# circuito_control.net
KiCad netlist of a schematic drawn in EAGLE
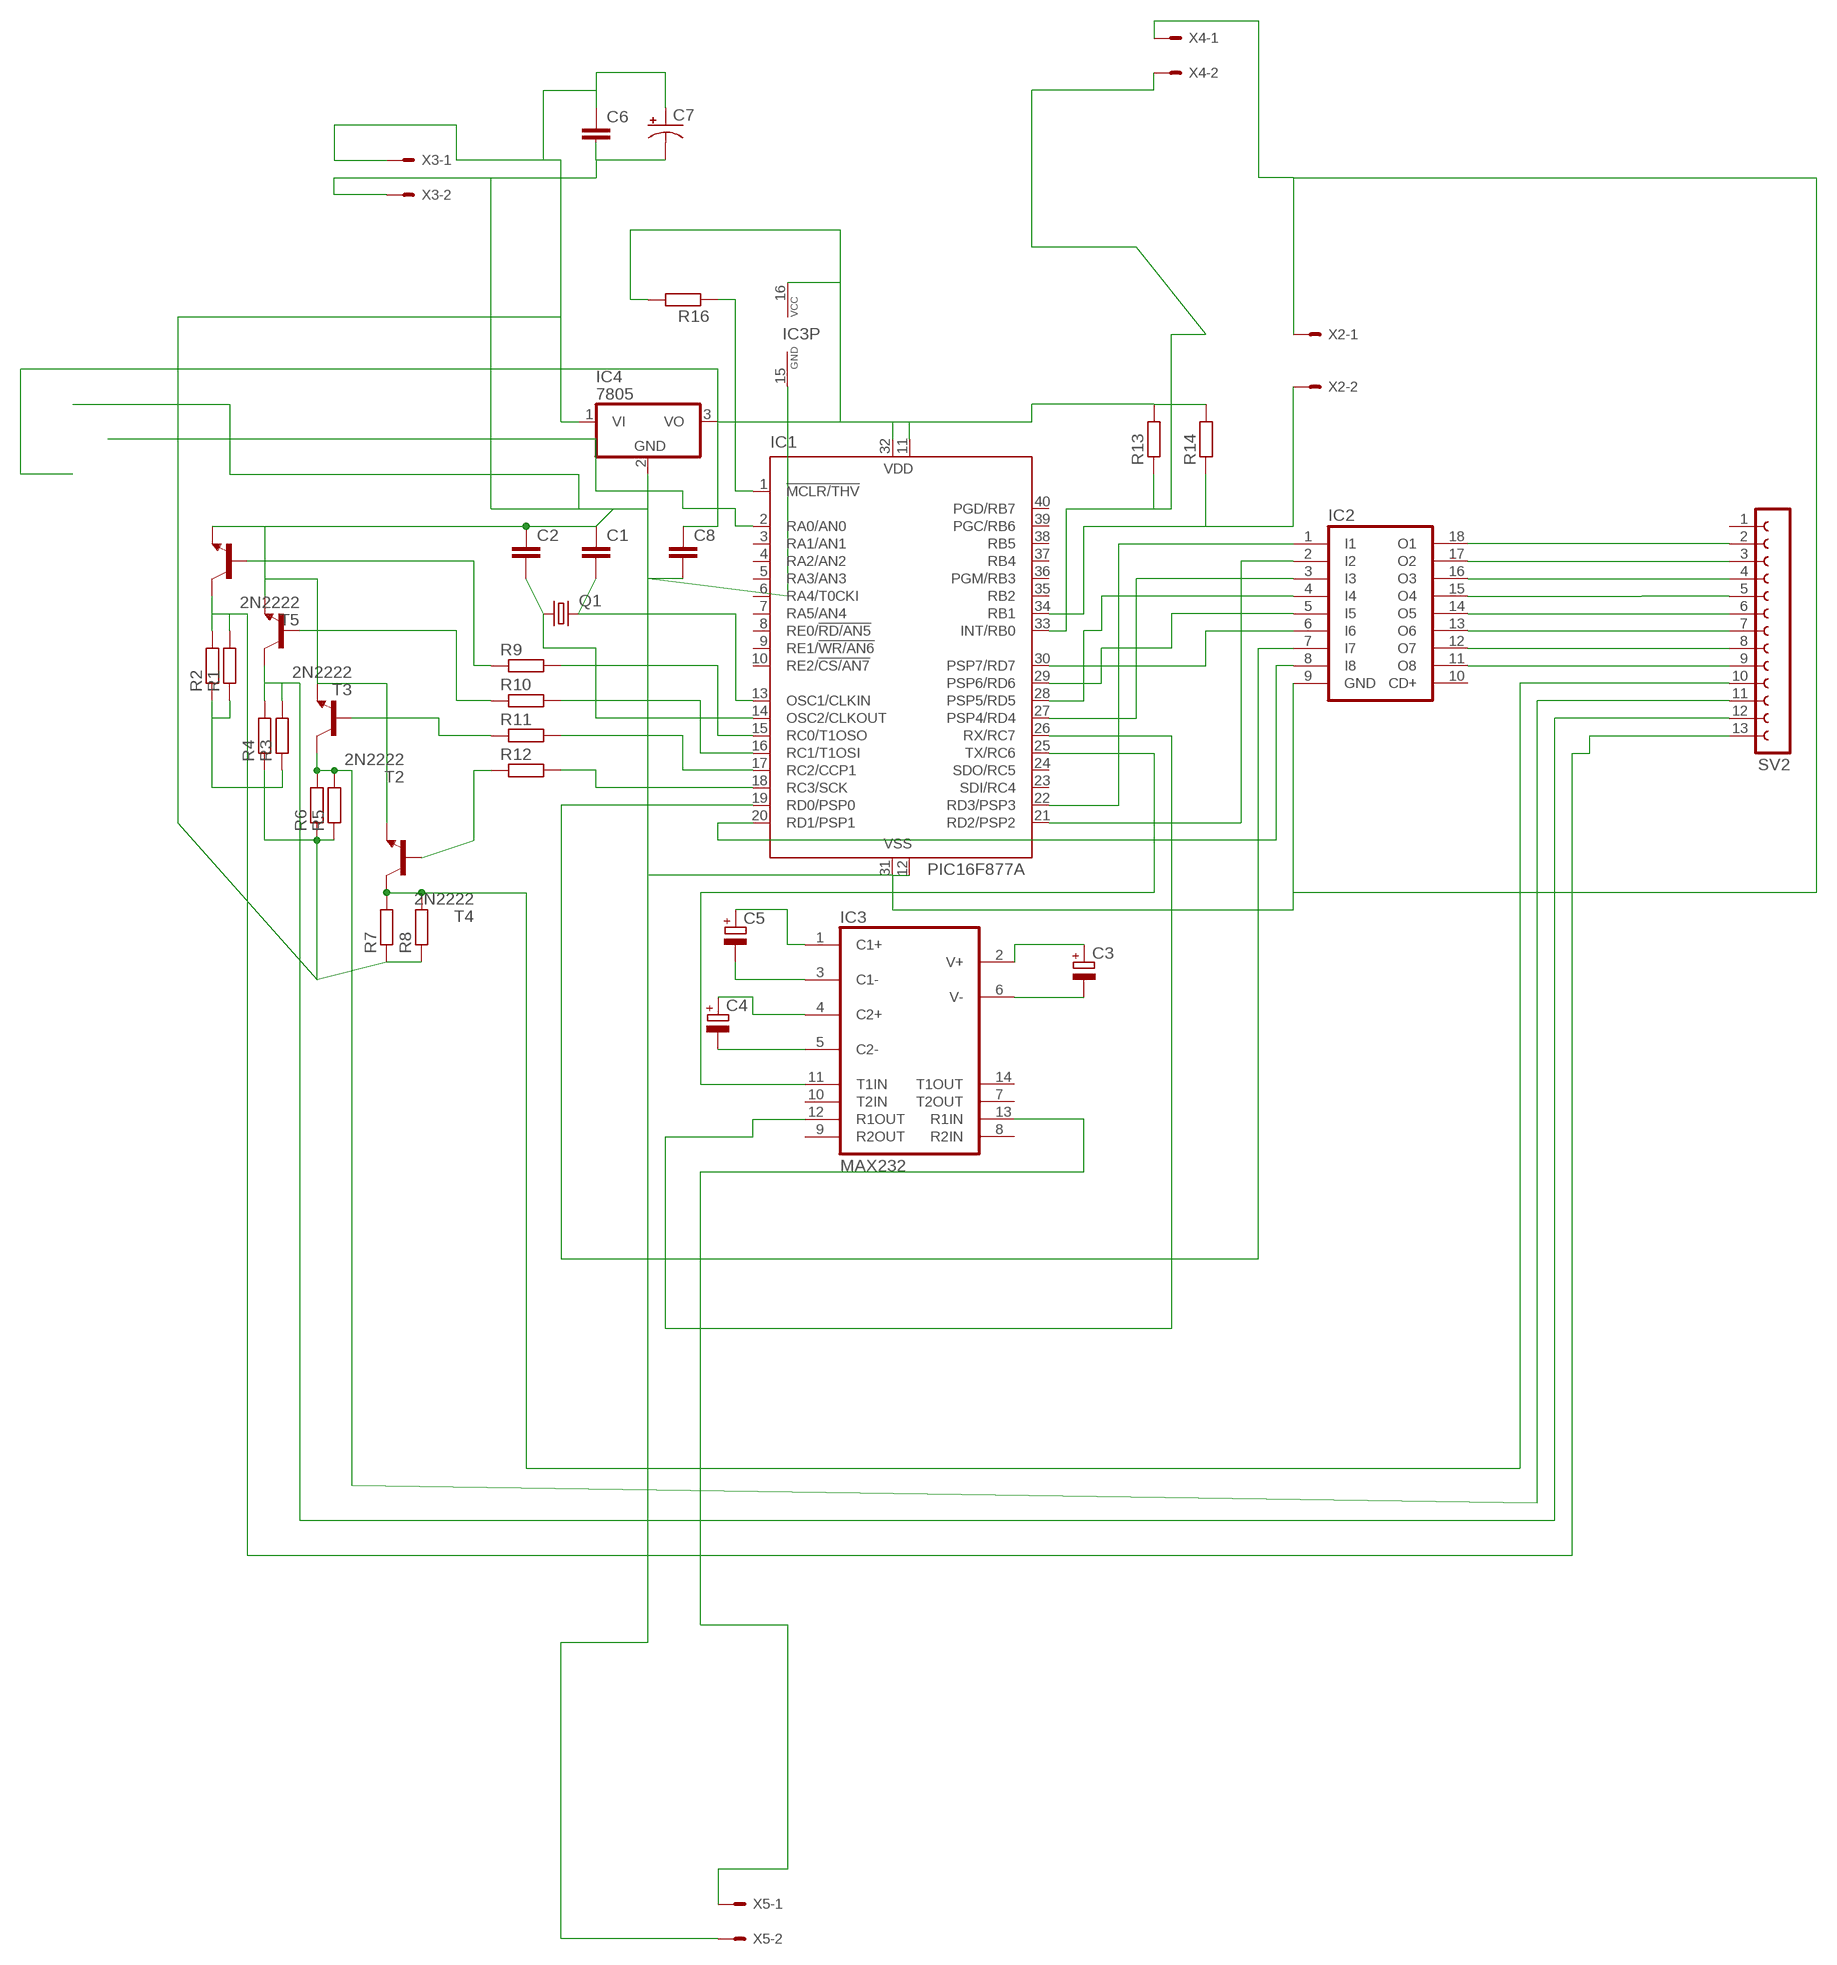
[diagram p0: schematic, sheet 1]

(export (version "E")
  (design (tool "Eeschema 10.0.6"))
  (components
    (comp (ref "C1")
      (value "C-EU025-025X050")
      (footprint "eagle-import:C025-025X050")
      (libsource (lib "eagle-import") (part "C-EU025-025X050"))
    )
    (comp (ref "C2")
      (value "C-EU025-025X050")
      (footprint "eagle-import:C025-025X050")
      (libsource (lib "eagle-import") (part "C-EU025-025X050"))
    )
    (comp (ref "C3")
      (value "CPOL-EUE1.8-4")
      (footprint "eagle-import:E1,8-4")
      (libsource (lib "eagle-import") (part "CPOL-EUE1.8-4"))
    )
    (comp (ref "C4")
      (value "CPOL-EUE1.8-4")
      (footprint "eagle-import:E1,8-4")
      (libsource (lib "eagle-import") (part "CPOL-EUE1.8-4"))
    )
    (comp (ref "C5")
      (value "CPOL-EUE1.8-4")
      (footprint "eagle-import:E1,8-4")
      (libsource (lib "eagle-import") (part "CPOL-EUE1.8-4"))
    )
    (comp (ref "C6")
      (value "C-EU025-025X050")
      (footprint "eagle-import:C025-025X050")
      (libsource (lib "eagle-import") (part "C-EU025-025X050"))
    )
    (comp (ref "C7")
      (value "CPOL-USE5-10.5")
      (footprint "eagle-import:E5-10,5")
      (libsource (lib "eagle-import") (part "CPOL-USE5-10.5"))
    )
    (comp (ref "C8")
      (value "C-EU025-025X050")
      (footprint "eagle-import:C025-025X050")
      (libsource (lib "eagle-import") (part "C-EU025-025X050"))
    )
    (comp (ref "IC1")
      (value "PIC16F877A")
      (footprint "eagle-import:DIL40")
      (fields (field (name "MF") "MICROCHIP") (field (name "MPN") "PIC16F877-04/P"))
      (libsource (lib "eagle-import") (part "PIC16F87P7"))
    )
    (comp (ref "IC2")
      (value "ULN2803A")
      (footprint "eagle-import:DIL18")
      (libsource (lib "eagle-import") (part "ULN2803A"))
    )
    (comp (ref "IC3")
      (value "MAX232")
      (footprint "eagle-import:DIL16")
      (fields (field (name "MF") "MAXIM") (field (name "MPN") "MAX232ACPE+"))
      (libsource (lib "eagle-import") (part "MAX232"))
    )
    (comp (ref "IC4")
      (value "7805")
      (footprint "eagle-import:TO220V")
      (libsource (lib "eagle-import") (part "78TV05"))
    )
    (comp (ref "Q1")
      (value "CRYSTALHC49U70")
      (footprint "eagle-import:HC49U70")
      (libsource (lib "eagle-import") (part "CRYSTALHC49U70"))
    )
    (comp (ref "R1")
      (value "R-EU_0411/15")
      (footprint "eagle-import:0411_15")
      (libsource (lib "eagle-import") (part "R-EU_0411/15"))
    )
    (comp (ref "R2")
      (value "R-EU_0411/15")
      (footprint "eagle-import:0411_15")
      (libsource (lib "eagle-import") (part "R-EU_0411/15"))
    )
    (comp (ref "R3")
      (value "R-EU_0411/15")
      (footprint "eagle-import:0411_15")
      (libsource (lib "eagle-import") (part "R-EU_0411/15"))
    )
    (comp (ref "R4")
      (value "R-EU_0411/15")
      (footprint "eagle-import:0411_15")
      (libsource (lib "eagle-import") (part "R-EU_0411/15"))
    )
    (comp (ref "R5")
      (value "R-EU_0411/15")
      (footprint "eagle-import:0411_15")
      (libsource (lib "eagle-import") (part "R-EU_0411/15"))
    )
    (comp (ref "R6")
      (value "R-EU_0411/15")
      (footprint "eagle-import:0411_15")
      (libsource (lib "eagle-import") (part "R-EU_0411/15"))
    )
    (comp (ref "R7")
      (value "R-EU_0411/15")
      (footprint "eagle-import:0411_15")
      (libsource (lib "eagle-import") (part "R-EU_0411/15"))
    )
    (comp (ref "R8")
      (value "R-EU_0411/15")
      (footprint "eagle-import:0411_15")
      (libsource (lib "eagle-import") (part "R-EU_0411/15"))
    )
    (comp (ref "R9")
      (value "R-EU_0207/7")
      (footprint "eagle-import:0207_7")
      (libsource (lib "eagle-import") (part "resistor_R-EU_0207/7"))
    )
    (comp (ref "R10")
      (value "R-EU_0207/7")
      (footprint "eagle-import:0207_7")
      (libsource (lib "eagle-import") (part "resistor_R-EU_0207/7"))
    )
    (comp (ref "R11")
      (value "R-EU_0207/7")
      (footprint "eagle-import:0207_7")
      (libsource (lib "eagle-import") (part "resistor_R-EU_0207/7"))
    )
    (comp (ref "R12")
      (value "R-EU_0207/7")
      (footprint "eagle-import:0207_7")
      (libsource (lib "eagle-import") (part "resistor_R-EU_0207/7"))
    )
    (comp (ref "R13")
      (value "R-EU_0207/7")
      (footprint "eagle-import:0207_7")
      (libsource (lib "eagle-import") (part "resistor_R-EU_0207/7"))
    )
    (comp (ref "R14")
      (value "R-EU_0207/7")
      (footprint "eagle-import:0207_7")
      (libsource (lib "eagle-import") (part "resistor_R-EU_0207/7"))
    )
    (comp (ref "R16")
      (value "R-EU_0207/7")
      (footprint "eagle-import:0207_7")
      (libsource (lib "eagle-import") (part "resistor_R-EU_0207/7"))
    )
    (comp (ref "SV2")
      (value "FE13-1")
      (footprint "eagle-import:FE13")
      (libsource (lib "eagle-import") (part "FE13-1"))
    )
    (comp (ref "T2")
      (value "2N2222")
      (footprint "eagle-import:TO18")
      (libsource (lib "eagle-import") (part "2N2222"))
    )
    (comp (ref "T3")
      (value "2N2222")
      (footprint "eagle-import:TO18")
      (libsource (lib "eagle-import") (part "2N2222"))
    )
    (comp (ref "T4")
      (value "2N2222")
      (footprint "eagle-import:TO18")
      (libsource (lib "eagle-import") (part "2N2222"))
    )
    (comp (ref "T5")
      (value "2N2222")
      (footprint "eagle-import:TO18")
      (libsource (lib "eagle-import") (part "2N2222"))
    )
    (comp (ref "X2")
      (value "KK-156-2")
      (footprint "eagle-import:KK-156-2")
      (libsource (lib "eagle-import") (part "KK-156-2"))
    )
    (comp (ref "X3")
      (value "KK-156-2")
      (footprint "eagle-import:KK-156-2")
      (libsource (lib "eagle-import") (part "KK-156-2"))
    )
    (comp (ref "X4")
      (value "KK-156-2")
      (footprint "eagle-import:KK-156-2")
      (libsource (lib "eagle-import") (part "KK-156-2"))
    )
    (comp (ref "X5")
      (value "KK-156-2")
      (footprint "eagle-import:KK-156-2")
      (fields (field (name "OC_FARNELL") "unknown") (field (name "OC_NEWARK") "unknown"))
      (libsource (lib "eagle-import") (part "KK-156-2"))
    )
  )
  (nets
    (net (code "1") (name "Net-(IC1-INT{slash}RB0)") (class "Default")
      (node (ref "IC1") (pin "33") (pinfunction "INT/RB0_33") (pintype "bidirectional"))
      (node (ref "R13") (pin "1") (pinfunction "1_1") (pintype "passive"))
      (node (ref "X4") (pin "2") (pinfunction "S_2") (pintype "passive"))
    )
    (net (code "2") (name "Net-(IC1-OSC1{slash}CLKIN)") (class "Default")
      (node (ref "C1") (pin "2") (pinfunction "2_2") (pintype "passive"))
      (node (ref "IC1") (pin "13") (pinfunction "OSC1/CLKIN_13") (pintype "input"))
      (node (ref "Q1") (pin "2") (pinfunction "2_2") (pintype "passive"))
    )
    (net (code "3") (name "Net-(IC1-OSC2{slash}CLKOUT)") (class "Default")
      (node (ref "C2") (pin "2") (pinfunction "2_2") (pintype "passive"))
      (node (ref "IC1") (pin "14") (pinfunction "OSC2/CLKOUT_14") (pintype "output"))
      (node (ref "Q1") (pin "1") (pinfunction "1_1") (pintype "passive"))
    )
    (net (code "4") (name "Net-(IC1-PSP4{slash}RD4)") (class "Default")
      (node (ref "IC1") (pin "27") (pinfunction "PSP4/RD4_27") (pintype "bidirectional"))
      (node (ref "IC2") (pin "3") (pinfunction "I3_3") (pintype "input"))
    )
    (net (code "5") (name "Net-(IC1-PSP5{slash}RD5)") (class "Default")
      (node (ref "IC1") (pin "28") (pinfunction "PSP5/RD5_28") (pintype "bidirectional"))
      (node (ref "IC2") (pin "4") (pinfunction "I4_4") (pintype "input"))
    )
    (net (code "6") (name "Net-(IC1-PSP6{slash}RD6)") (class "Default")
      (node (ref "IC1") (pin "29") (pinfunction "PSP6/RD6_29") (pintype "bidirectional"))
      (node (ref "IC2") (pin "5") (pinfunction "I5_5") (pintype "input"))
    )
    (net (code "7") (name "Net-(IC1-PSP7{slash}RD7)") (class "Default")
      (node (ref "IC1") (pin "30") (pinfunction "PSP7/RD7_30") (pintype "bidirectional"))
      (node (ref "IC2") (pin "6") (pinfunction "I6_6") (pintype "input"))
    )
    (net (code "8") (name "Net-(IC1-RB1)") (class "Default")
      (node (ref "IC1") (pin "34") (pinfunction "RB1_34") (pintype "bidirectional"))
      (node (ref "R14") (pin "1") (pinfunction "1_1") (pintype "passive"))
      (node (ref "X2") (pin "2") (pinfunction "S_2") (pintype "passive"))
    )
    (net (code "9") (name "Net-(IC1-RC0{slash}T1OSO)") (class "Default")
      (node (ref "IC1") (pin "15") (pinfunction "RC0/T1OSO_15") (pintype "bidirectional"))
      (node (ref "R9") (pin "2") (pinfunction "2_2") (pintype "passive"))
    )
    (net (code "10") (name "Net-(IC1-RC1{slash}T1OSI)") (class "Default")
      (node (ref "IC1") (pin "16") (pinfunction "RC1/T1OSI_16") (pintype "bidirectional"))
      (node (ref "R10") (pin "2") (pinfunction "2_2") (pintype "passive"))
    )
    (net (code "11") (name "Net-(IC1-RC2{slash}CCP1)") (class "Default")
      (node (ref "IC1") (pin "17") (pinfunction "RC2/CCP1_17") (pintype "bidirectional"))
      (node (ref "R11") (pin "2") (pinfunction "2_2") (pintype "passive"))
    )
    (net (code "12") (name "Net-(IC1-RC3{slash}SCK)") (class "Default")
      (node (ref "IC1") (pin "18") (pinfunction "RC3/SCK_18") (pintype "bidirectional"))
      (node (ref "R12") (pin "2") (pinfunction "2_2") (pintype "passive"))
    )
    (net (code "13") (name "Net-(IC1-RD0{slash}PSP0)") (class "Default")
      (node (ref "IC1") (pin "19") (pinfunction "RD0/PSP0_19") (pintype "bidirectional"))
      (node (ref "IC2") (pin "7") (pinfunction "I7_7") (pintype "input"))
    )
    (net (code "14") (name "Net-(IC1-RD1{slash}PSP1)") (class "Default")
      (node (ref "IC1") (pin "20") (pinfunction "RD1/PSP1_20") (pintype "bidirectional"))
      (node (ref "IC2") (pin "8") (pinfunction "I8_8") (pintype "input"))
    )
    (net (code "15") (name "Net-(IC1-RD2{slash}PSP2)") (class "Default")
      (node (ref "IC1") (pin "21") (pinfunction "RD2/PSP2_21") (pintype "bidirectional"))
      (node (ref "IC2") (pin "2") (pinfunction "I2_2") (pintype "input"))
    )
    (net (code "16") (name "Net-(IC1-RD3{slash}PSP3)") (class "Default")
      (node (ref "IC1") (pin "22") (pinfunction "RD3/PSP3_22") (pintype "bidirectional"))
      (node (ref "IC2") (pin "1") (pinfunction "I1_1") (pintype "input"))
    )
    (net (code "17") (name "Net-(IC1-RX{slash}RC7)") (class "Default")
      (node (ref "IC1") (pin "26") (pinfunction "RX/RC7_26") (pintype "bidirectional"))
      (node (ref "IC3") (pin "12") (pinfunction "R1OUT_12") (pintype "output"))
    )
    (net (code "18") (name "Net-(IC1-TX{slash}RC6)") (class "Default")
      (node (ref "IC1") (pin "25") (pinfunction "TX/RC6_25") (pintype "bidirectional"))
      (node (ref "IC3") (pin "11") (pinfunction "T1IN_11") (pintype "input"))
    )
    (net (code "19") (name "Net-(IC1-~{MCLR{slash}THV})") (class "Default")
      (node (ref "IC1") (pin "1") (pinfunction "~{MCLR/THV}_1") (pintype "input"))
      (node (ref "R16") (pin "1") (pinfunction "1_1") (pintype "passive"))
    )
    (net (code "20") (name "Net-(IC2-GND)") (class "Default")
      (node (ref "C1") (pin "1") (pinfunction "1_1") (pintype "passive"))
      (node (ref "C2") (pin "1") (pinfunction "1_1") (pintype "passive"))
      (node (ref "C6") (pin "2") (pinfunction "2_2") (pintype "passive"))
      (node (ref "C7") (pin "-") (pinfunction "-_-") (pintype "passive"))
      (node (ref "C8") (pin "2") (pinfunction "2_2") (pintype "passive"))
      (node (ref "IC1") (pin "12") (pinfunction "VSS_12") (pintype "power_in"))
      (node (ref "IC1") (pin "31") (pinfunction "VSS_31") (pintype "power_in"))
      (node (ref "IC2") (pin "9") (pinfunction "GND_9") (pintype "power_in"))
      (node (ref "IC3") (pin "15") (pinfunction "GND_15") (pintype "power_in"))
      (node (ref "IC4") (pin "2") (pinfunction "GND_2") (pintype "passive"))
      (node (ref "T2") (pin "1") (pinfunction "E_1") (pintype "passive"))
      (node (ref "T3") (pin "1") (pinfunction "E_1") (pintype "passive"))
      (node (ref "T4") (pin "1") (pinfunction "E_1") (pintype "passive"))
      (node (ref "T5") (pin "1") (pinfunction "E_1") (pintype "passive"))
      (node (ref "X2") (pin "1") (pinfunction "S_1") (pintype "passive"))
      (node (ref "X3") (pin "2") (pinfunction "S_2") (pintype "passive"))
      (node (ref "X4") (pin "1") (pinfunction "S_1") (pintype "passive"))
      (node (ref "X5") (pin "2") (pinfunction "S_2") (pintype "passive"))
    )
    (net (code "21") (name "Net-(IC2-O1)") (class "Default")
      (node (ref "IC2") (pin "18") (pinfunction "O1_18") (pintype "open_collector"))
      (node (ref "SV2") (pin "2") (pinfunction "2_2") (pintype "passive"))
    )
    (net (code "22") (name "Net-(IC2-O2)") (class "Default")
      (node (ref "IC2") (pin "17") (pinfunction "O2_17") (pintype "open_collector"))
      (node (ref "SV2") (pin "3") (pinfunction "3_3") (pintype "passive"))
    )
    (net (code "23") (name "Net-(IC2-O3)") (class "Default")
      (node (ref "IC2") (pin "16") (pinfunction "O3_16") (pintype "open_collector"))
      (node (ref "SV2") (pin "4") (pinfunction "4_4") (pintype "passive"))
    )
    (net (code "24") (name "Net-(IC2-O4)") (class "Default")
      (node (ref "IC2") (pin "15") (pinfunction "O4_15") (pintype "open_collector"))
      (node (ref "SV2") (pin "5") (pinfunction "5_5") (pintype "passive"))
    )
    (net (code "25") (name "Net-(IC2-O5)") (class "Default")
      (node (ref "IC2") (pin "14") (pinfunction "O5_14") (pintype "open_collector"))
      (node (ref "SV2") (pin "6") (pinfunction "6_6") (pintype "passive"))
    )
    (net (code "26") (name "Net-(IC2-O6)") (class "Default")
      (node (ref "IC2") (pin "13") (pinfunction "O6_13") (pintype "open_collector"))
      (node (ref "SV2") (pin "7") (pinfunction "7_7") (pintype "passive"))
    )
    (net (code "27") (name "Net-(IC2-O7)") (class "Default")
      (node (ref "IC2") (pin "12") (pinfunction "O7_12") (pintype "open_collector"))
      (node (ref "SV2") (pin "8") (pinfunction "8_8") (pintype "passive"))
    )
    (net (code "28") (name "Net-(IC2-O8)") (class "Default")
      (node (ref "IC2") (pin "11") (pinfunction "O8_11") (pintype "open_collector"))
      (node (ref "SV2") (pin "9") (pinfunction "9_9") (pintype "passive"))
    )
    (net (code "29") (name "Net-(IC3A-C1+)") (class "Default")
      (node (ref "C5") (pin "+") (pinfunction "+_+") (pintype "passive"))
      (node (ref "IC3") (pin "1") (pinfunction "C1+_1") (pintype "bidirectional"))
    )
    (net (code "30") (name "Net-(IC3A-C1-)") (class "Default")
      (node (ref "C5") (pin "-") (pinfunction "-_-") (pintype "passive"))
      (node (ref "IC3") (pin "3") (pinfunction "C1-_3") (pintype "bidirectional"))
    )
    (net (code "31") (name "Net-(IC3A-C2+)") (class "Default")
      (node (ref "C4") (pin "+") (pinfunction "+_+") (pintype "passive"))
      (node (ref "IC3") (pin "4") (pinfunction "C2+_4") (pintype "bidirectional"))
    )
    (net (code "32") (name "Net-(IC3A-C2-)") (class "Default")
      (node (ref "C4") (pin "-") (pinfunction "-_-") (pintype "passive"))
      (node (ref "IC3") (pin "5") (pinfunction "C2-_5") (pintype "bidirectional"))
    )
    (net (code "33") (name "Net-(IC3A-R1IN)") (class "Default")
      (node (ref "IC3") (pin "13") (pinfunction "R1IN_13") (pintype "input"))
      (node (ref "X5") (pin "1") (pinfunction "S_1") (pintype "passive"))
    )
    (net (code "34") (name "Net-(IC3A-V+)") (class "Default")
      (node (ref "C3") (pin "+") (pinfunction "+_+") (pintype "passive"))
      (node (ref "IC3") (pin "2") (pinfunction "V+_2") (pintype "bidirectional"))
    )
    (net (code "35") (name "Net-(IC3A-V-)") (class "Default")
      (node (ref "C3") (pin "-") (pinfunction "-_-") (pintype "passive"))
      (node (ref "IC3") (pin "6") (pinfunction "V-_6") (pintype "bidirectional"))
    )
    (net (code "36") (name "Net-(IC3B-VCC)") (class "Default")
      (node (ref "C8") (pin "1") (pinfunction "1_1") (pintype "passive"))
      (node (ref "IC1") (pin "11") (pinfunction "VDD_11") (pintype "power_in"))
      (node (ref "IC1") (pin "32") (pinfunction "VDD_32") (pintype "power_in"))
      (node (ref "IC3") (pin "16") (pinfunction "VCC_16") (pintype "power_in"))
      (node (ref "IC4") (pin "3") (pinfunction "VO_3") (pintype "passive"))
      (node (ref "R13") (pin "2") (pinfunction "2_2") (pintype "passive"))
      (node (ref "R14") (pin "2") (pinfunction "2_2") (pintype "passive"))
      (node (ref "R16") (pin "2") (pinfunction "2_2") (pintype "passive"))
    )
    (net (code "37") (name "Net-(IC4-VI)") (class "Default")
      (node (ref "C6") (pin "1") (pinfunction "1_1") (pintype "passive"))
      (node (ref "C7") (pin "+") (pinfunction "+_+") (pintype "passive"))
      (node (ref "IC4") (pin "1") (pinfunction "VI_1") (pintype "input"))
      (node (ref "R1") (pin "1") (pinfunction "1_1") (pintype "passive"))
      (node (ref "R2") (pin "1") (pinfunction "1_1") (pintype "passive"))
      (node (ref "R3") (pin "1") (pinfunction "1_1") (pintype "passive"))
      (node (ref "R4") (pin "1") (pinfunction "1_1") (pintype "passive"))
      (node (ref "R5") (pin "1") (pinfunction "1_1") (pintype "passive"))
      (node (ref "R6") (pin "1") (pinfunction "1_1") (pintype "passive"))
      (node (ref "R7") (pin "1") (pinfunction "1_1") (pintype "passive"))
      (node (ref "R8") (pin "1") (pinfunction "1_1") (pintype "passive"))
      (node (ref "X3") (pin "1") (pinfunction "S_1") (pintype "passive"))
    )
    (net (code "38") (name "Net-(T2-B)") (class "Default")
      (node (ref "R11") (pin "1") (pinfunction "1_1") (pintype "passive"))
      (node (ref "T2") (pin "2") (pinfunction "B_2") (pintype "passive"))
    )
    (net (code "39") (name "Net-(T2-C)") (class "Default")
      (node (ref "R5") (pin "2") (pinfunction "2_2") (pintype "passive"))
      (node (ref "R6") (pin "2") (pinfunction "2_2") (pintype "passive"))
      (node (ref "SV2") (pin "11") (pinfunction "11_11") (pintype "passive"))
      (node (ref "T2") (pin "3") (pinfunction "C_3") (pintype "passive"))
    )
    (net (code "40") (name "Net-(T3-B)") (class "Default")
      (node (ref "R10") (pin "1") (pinfunction "1_1") (pintype "passive"))
      (node (ref "T3") (pin "2") (pinfunction "B_2") (pintype "passive"))
    )
    (net (code "41") (name "Net-(T3-C)") (class "Default")
      (node (ref "R3") (pin "2") (pinfunction "2_2") (pintype "passive"))
      (node (ref "R4") (pin "2") (pinfunction "2_2") (pintype "passive"))
      (node (ref "SV2") (pin "12") (pinfunction "12_12") (pintype "passive"))
      (node (ref "T3") (pin "3") (pinfunction "C_3") (pintype "passive"))
    )
    (net (code "42") (name "Net-(T4-B)") (class "Default")
      (node (ref "R12") (pin "1") (pinfunction "1_1") (pintype "passive"))
      (node (ref "T4") (pin "2") (pinfunction "B_2") (pintype "passive"))
    )
    (net (code "43") (name "Net-(T4-C)") (class "Default")
      (node (ref "R7") (pin "2") (pinfunction "2_2") (pintype "passive"))
      (node (ref "R8") (pin "2") (pinfunction "2_2") (pintype "passive"))
      (node (ref "SV2") (pin "10") (pinfunction "10_10") (pintype "passive"))
      (node (ref "T4") (pin "3") (pinfunction "C_3") (pintype "passive"))
    )
    (net (code "44") (name "Net-(T5-B)") (class "Default")
      (node (ref "R9") (pin "1") (pinfunction "1_1") (pintype "passive"))
      (node (ref "T5") (pin "2") (pinfunction "B_2") (pintype "passive"))
    )
    (net (code "45") (name "Net-(T5-C)") (class "Default")
      (node (ref "R1") (pin "2") (pinfunction "2_2") (pintype "passive"))
      (node (ref "R2") (pin "2") (pinfunction "2_2") (pintype "passive"))
      (node (ref "SV2") (pin "13") (pinfunction "13_13") (pintype "passive"))
      (node (ref "T5") (pin "3") (pinfunction "C_3") (pintype "passive"))
    )
    (net (code "46") (name "unconnected-(IC1-PGC{slash}RB6-Pad39)") (class "Default")
      (node (ref "IC1") (pin "39") (pinfunction "PGC/RB6_39") (pintype "bidirectional"))
    )
    (net (code "47") (name "unconnected-(IC1-PGD{slash}RB7-Pad40)") (class "Default")
      (node (ref "IC1") (pin "40") (pinfunction "PGD/RB7_40") (pintype "bidirectional"))
    )
    (net (code "48") (name "unconnected-(IC1-PGM{slash}RB3-Pad36)") (class "Default")
      (node (ref "IC1") (pin "36") (pinfunction "PGM/RB3_36") (pintype "bidirectional"))
    )
    (net (code "49") (name "unconnected-(IC1-RA0{slash}AN0-Pad2)") (class "Default")
      (node (ref "IC1") (pin "2") (pinfunction "RA0/AN0_2") (pintype "bidirectional"))
    )
    (net (code "50") (name "unconnected-(IC1-RA1{slash}AN1-Pad3)") (class "Default")
      (node (ref "IC1") (pin "3") (pinfunction "RA1/AN1_3") (pintype "bidirectional"))
    )
    (net (code "51") (name "unconnected-(IC1-RA2{slash}AN2-Pad4)") (class "Default")
      (node (ref "IC1") (pin "4") (pinfunction "RA2/AN2_4") (pintype "bidirectional"))
    )
    (net (code "52") (name "unconnected-(IC1-RA3{slash}AN3-Pad5)") (class "Default")
      (node (ref "IC1") (pin "5") (pinfunction "RA3/AN3_5") (pintype "bidirectional"))
    )
    (net (code "53") (name "unconnected-(IC1-RA4{slash}T0CKI-Pad6)") (class "Default")
      (node (ref "IC1") (pin "6") (pinfunction "RA4/T0CKI_6") (pintype "bidirectional"))
    )
    (net (code "54") (name "unconnected-(IC1-RA5{slash}AN4-Pad7)") (class "Default")
      (node (ref "IC1") (pin "7") (pinfunction "RA5/AN4_7") (pintype "bidirectional"))
    )
    (net (code "55") (name "unconnected-(IC1-RB2-Pad35)") (class "Default")
      (node (ref "IC1") (pin "35") (pinfunction "RB2_35") (pintype "bidirectional"))
    )
    (net (code "56") (name "unconnected-(IC1-RB4-Pad37)") (class "Default")
      (node (ref "IC1") (pin "37") (pinfunction "RB4_37") (pintype "bidirectional"))
    )
    (net (code "57") (name "unconnected-(IC1-RB5-Pad38)") (class "Default")
      (node (ref "IC1") (pin "38") (pinfunction "RB5_38") (pintype "bidirectional"))
    )
    (net (code "58") (name "unconnected-(IC1-RE0{slash}~{RD{slash}AN5}-Pad8)") (class "Default")
      (node (ref "IC1") (pin "8") (pinfunction "RE0/~{RD/AN5}_8") (pintype "bidirectional"))
    )
    (net (code "59") (name "unconnected-(IC1-RE1{slash}~{WR{slash}AN6}-Pad9)") (class "Default")
      (node (ref "IC1") (pin "9") (pinfunction "RE1/~{WR/AN6}_9") (pintype "bidirectional"))
    )
    (net (code "60") (name "unconnected-(IC1-RE2{slash}~{CS{slash}AN7}-Pad10)") (class "Default")
      (node (ref "IC1") (pin "10") (pinfunction "RE2/~{CS/AN7}_10") (pintype "bidirectional"))
    )
    (net (code "61") (name "unconnected-(IC1-SDI{slash}RC4-Pad23)") (class "Default")
      (node (ref "IC1") (pin "23") (pinfunction "SDI/RC4_23") (pintype "bidirectional"))
    )
    (net (code "62") (name "unconnected-(IC1-SDO{slash}RC5-Pad24)") (class "Default")
      (node (ref "IC1") (pin "24") (pinfunction "SDO/RC5_24") (pintype "bidirectional"))
    )
    (net (code "63") (name "unconnected-(IC2-CD+-Pad10)") (class "Default")
      (node (ref "IC2") (pin "10") (pinfunction "CD+_10") (pintype "passive"))
    )
    (net (code "64") (name "unconnected-(IC3A-R2IN-Pad8)") (class "Default")
      (node (ref "IC3") (pin "8") (pinfunction "R2IN_8") (pintype "input"))
    )
    (net (code "65") (name "unconnected-(IC3A-R2OUT-Pad9)") (class "Default")
      (node (ref "IC3") (pin "9") (pinfunction "R2OUT_9") (pintype "output"))
    )
    (net (code "66") (name "unconnected-(IC3A-T1OUT-Pad14)") (class "Default")
      (node (ref "IC3") (pin "14") (pinfunction "T1OUT_14") (pintype "output"))
    )
    (net (code "67") (name "unconnected-(IC3A-T2IN-Pad10)") (class "Default")
      (node (ref "IC3") (pin "10") (pinfunction "T2IN_10") (pintype "input"))
    )
    (net (code "68") (name "unconnected-(IC3A-T2OUT-Pad7)") (class "Default")
      (node (ref "IC3") (pin "7") (pinfunction "T2OUT_7") (pintype "output"))
    )
    (net (code "69") (name "unconnected-(SV2-Pad1)") (class "Default")
      (node (ref "SV2") (pin "1") (pinfunction "1_1") (pintype "passive"))
    )
  )
)
